# 3_Connectors.net
KiCad netlist of a schematic drawn in Altium Designer
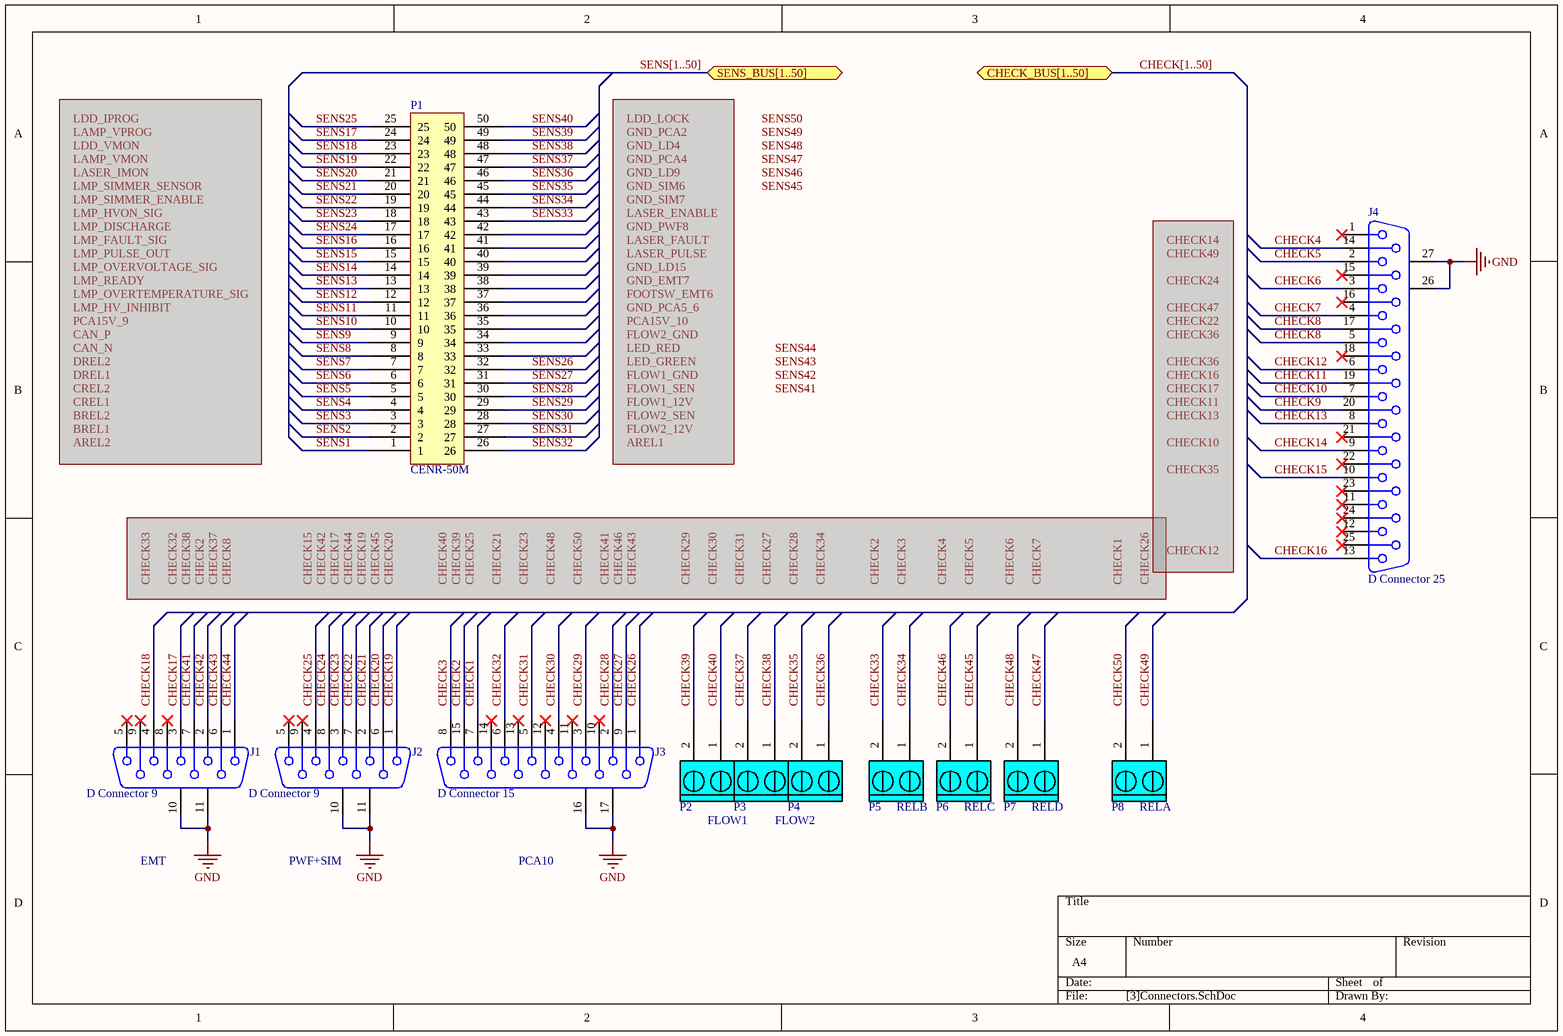
[diagram p0: [3]Connectors.SchDoc]

(export (version "E")
  (design (tool "Eeschema 10.0.6"))
  (components
    (comp (ref "J1")
      (value "D Connector 9")
      (footprint "DSUB1.385-2H9F")
      (description "Receptacle Assembly, 9 Position, Right Angle")
      (fields (field (name "PUBLISHER") "Altium Limited"))
      (libsource (lib "Connectors") (part "D Connector 9"))
    )
    (comp (ref "J2")
      (value "D Connector 9")
      (footprint "DSUB1.385-2H9M")
      (description "Receptacle Assembly, 9 Position, Right Angle")
      (fields (field (name "PUBLISHER") "Altium Limited"))
      (libsource (lib "Connectors") (part "D Connector 9"))
    )
    (comp (ref "J3")
      (value "D Connector 15")
      (footprint "DSUB1.385-2H15M")
      (description "Receptacle Assembly, 15 Position, Right Angle")
      (fields (field (name "PUBLISHER") "Altium Limited"))
      (libsource (lib "Connectors") (part "D Connector 15"))
    )
    (comp (ref "J4")
      (value "D Connector 25")
      (footprint "DSUB1.385-2H25A-F")
      (description "Receptacle Assembly, 25 Position, Right Angle")
      (fields (field (name "PUBLISHER") "Altium Limited"))
      (libsource (lib "Connectors") (part "D Connector 25"))
    )
    (comp (ref "P1")
      (value "CENR-50M")
      (footprint "CENR-50M")
      (libsource (lib "Connectors") (part "CENR-50M"))
    )
    (comp (ref "P2")
      (value "DG340-3.81")
      (footprint "DG340-3.81-02P-00A(H)")
      (description "Terminal block")
      (libsource (lib "Connectors") (part "DG340-3.81-02P"))
    )
    (comp (ref "P3")
      (value "DG340-3.81")
      (footprint "DG340-3.81-02P-00A(H)")
      (description "Terminal block")
      (libsource (lib "Connectors") (part "DG340-3.81-02P"))
    )
    (comp (ref "P4")
      (value "DG340-3.81")
      (footprint "DG340-3.81-02P-00A(H)")
      (description "Terminal block")
      (libsource (lib "Connectors") (part "DG340-3.81-02P"))
    )
    (comp (ref "P5")
      (value "DG340-3.81")
      (footprint "DG340-3.81-02P-00A(H)")
      (description "Terminal block")
      (libsource (lib "Connectors") (part "DG340-3.81-02P"))
    )
    (comp (ref "P6")
      (value "DG340-3.81")
      (footprint "DG340-3.81-02P-00A(H)")
      (description "Terminal block")
      (libsource (lib "Connectors") (part "DG340-3.81-02P"))
    )
    (comp (ref "P7")
      (value "DG340-3.81")
      (footprint "DG340-3.81-02P-00A(H)")
      (description "Terminal block")
      (libsource (lib "Connectors") (part "DG340-3.81-02P"))
    )
    (comp (ref "P8")
      (value "DG340-3.81")
      (footprint "DG340-3.81-02P-00A(H)")
      (description "Terminal block")
      (libsource (lib "Connectors") (part "DG340-3.81-02P"))
    )
  )
  (nets
    (net (code "7") (name "/CHECK1") (class "Default")
      (node (ref "J3") (pin "7") (pinfunction "7_7") (pintype "passive"))
    )
    (net (code "8") (name "/CHECK2") (class "Default")
      (node (ref "J3") (pin "15") (pinfunction "15_15") (pintype "passive"))
    )
    (net (code "9") (name "/CHECK3") (class "Default")
      (node (ref "J3") (pin "8") (pinfunction "8_8") (pintype "passive"))
    )
    (net (code "10") (name "/CHECK4") (class "Default")
      (node (ref "J4") (pin "14") (pinfunction "14_14") (pintype "passive"))
    )
    (net (code "11") (name "/CHECK5") (class "Default")
      (node (ref "J4") (pin "2") (pinfunction "2_2") (pintype "passive"))
    )
    (net (code "12") (name "/CHECK6") (class "Default")
      (node (ref "J4") (pin "3") (pinfunction "3_3") (pintype "passive"))
    )
    (net (code "13") (name "/CHECK7") (class "Default")
      (node (ref "J4") (pin "4") (pinfunction "4_4") (pintype "passive"))
    )
    (net (code "14") (name "/CHECK8") (class "Default")
      (node (ref "J4") (pin "17") (pinfunction "17_17") (pintype "passive"))
      (node (ref "J4") (pin "5") (pinfunction "5_5") (pintype "passive"))
    )
    (net (code "15") (name "/CHECK9") (class "Default")
      (node (ref "J4") (pin "20") (pinfunction "20_20") (pintype "passive"))
    )
    (net (code "16") (name "/CHECK10") (class "Default")
      (node (ref "J4") (pin "7") (pinfunction "7_7") (pintype "passive"))
    )
    (net (code "17") (name "/CHECK11") (class "Default")
      (node (ref "J4") (pin "19") (pinfunction "19_19") (pintype "passive"))
    )
    (net (code "18") (name "/CHECK12") (class "Default")
      (node (ref "J4") (pin "6") (pinfunction "6_6") (pintype "passive"))
    )
    (net (code "19") (name "/CHECK13") (class "Default")
      (node (ref "J4") (pin "8") (pinfunction "8_8") (pintype "passive"))
    )
    (net (code "20") (name "/CHECK14") (class "Default")
      (node (ref "J4") (pin "9") (pinfunction "9_9") (pintype "passive"))
    )
    (net (code "21") (name "/CHECK15") (class "Default")
      (node (ref "J4") (pin "10") (pinfunction "10_10") (pintype "passive"))
    )
    (net (code "22") (name "/CHECK16") (class "Default")
      (node (ref "J4") (pin "13") (pinfunction "13_13") (pintype "passive"))
    )
    (net (code "23") (name "/CHECK17") (class "Default")
      (node (ref "J1") (pin "3") (pinfunction "3_3") (pintype "passive"))
    )
    (net (code "24") (name "/CHECK18") (class "Default")
      (node (ref "J1") (pin "4") (pinfunction "4_4") (pintype "passive"))
    )
    (net (code "25") (name "/CHECK19") (class "Default")
      (node (ref "J2") (pin "1") (pinfunction "1_1") (pintype "passive"))
    )
    (net (code "26") (name "/CHECK20") (class "Default")
      (node (ref "J2") (pin "6") (pinfunction "6_6") (pintype "passive"))
    )
    (net (code "27") (name "/CHECK21") (class "Default")
      (node (ref "J2") (pin "2") (pinfunction "2_2") (pintype "passive"))
    )
    (net (code "28") (name "/CHECK22") (class "Default")
      (node (ref "J2") (pin "7") (pinfunction "7_7") (pintype "passive"))
    )
    (net (code "29") (name "/CHECK23") (class "Default")
      (node (ref "J2") (pin "3") (pinfunction "3_3") (pintype "passive"))
    )
    (net (code "30") (name "/CHECK24") (class "Default")
      (node (ref "J2") (pin "8") (pinfunction "8_8") (pintype "passive"))
    )
    (net (code "31") (name "/CHECK25") (class "Default")
      (node (ref "J2") (pin "4") (pinfunction "4_4") (pintype "passive"))
    )
    (net (code "32") (name "/CHECK26") (class "Default")
      (node (ref "J3") (pin "1") (pinfunction "1_1") (pintype "passive"))
    )
    (net (code "33") (name "/CHECK27") (class "Default")
      (node (ref "J3") (pin "9") (pinfunction "9_9") (pintype "passive"))
    )
    (net (code "34") (name "/CHECK28") (class "Default")
      (node (ref "J3") (pin "2") (pinfunction "2_2") (pintype "passive"))
    )
    (net (code "35") (name "/CHECK29") (class "Default")
      (node (ref "J3") (pin "3") (pinfunction "3_3") (pintype "passive"))
    )
    (net (code "36") (name "/CHECK30") (class "Default")
      (node (ref "J3") (pin "4") (pinfunction "4_4") (pintype "passive"))
    )
    (net (code "37") (name "/CHECK31") (class "Default")
      (node (ref "J3") (pin "5") (pinfunction "5_5") (pintype "passive"))
    )
    (net (code "38") (name "/CHECK32") (class "Default")
      (node (ref "J3") (pin "6") (pinfunction "6_6") (pintype "passive"))
    )
    (net (code "39") (name "/CHECK33") (class "Default")
      (node (ref "P5") (pin "2") (pinfunction "2_2") (pintype "passive"))
    )
    (net (code "40") (name "/CHECK34") (class "Default")
      (node (ref "P5") (pin "1") (pinfunction "1_1") (pintype "passive"))
    )
    (net (code "41") (name "/CHECK35") (class "Default")
      (node (ref "P4") (pin "2") (pinfunction "2_2") (pintype "passive"))
    )
    (net (code "42") (name "/CHECK36") (class "Default")
      (node (ref "P4") (pin "1") (pinfunction "1_1") (pintype "passive"))
    )
    (net (code "43") (name "/CHECK37") (class "Default")
      (node (ref "P3") (pin "2") (pinfunction "2_2") (pintype "passive"))
    )
    (net (code "44") (name "/CHECK38") (class "Default")
      (node (ref "P3") (pin "1") (pinfunction "1_1") (pintype "passive"))
    )
    (net (code "45") (name "/CHECK39") (class "Default")
      (node (ref "P2") (pin "2") (pinfunction "2_2") (pintype "passive"))
    )
    (net (code "46") (name "/CHECK40") (class "Default")
      (node (ref "P2") (pin "1") (pinfunction "1_1") (pintype "passive"))
    )
    (net (code "47") (name "/CHECK41") (class "Default")
      (node (ref "J1") (pin "7") (pinfunction "7_7") (pintype "passive"))
    )
    (net (code "48") (name "/CHECK42") (class "Default")
      (node (ref "J1") (pin "2") (pinfunction "2_2") (pintype "passive"))
    )
    (net (code "49") (name "/CHECK43") (class "Default")
      (node (ref "J1") (pin "6") (pinfunction "6_6") (pintype "passive"))
    )
    (net (code "50") (name "/CHECK44") (class "Default")
      (node (ref "J1") (pin "1") (pinfunction "1_1") (pintype "passive"))
    )
    (net (code "51") (name "/CHECK45") (class "Default")
      (node (ref "P6") (pin "1") (pinfunction "1_1") (pintype "passive"))
    )
    (net (code "52") (name "/CHECK46") (class "Default")
      (node (ref "P6") (pin "2") (pinfunction "2_2") (pintype "passive"))
    )
    (net (code "53") (name "/CHECK47") (class "Default")
      (node (ref "P7") (pin "1") (pinfunction "1_1") (pintype "passive"))
    )
    (net (code "54") (name "/CHECK48") (class "Default")
      (node (ref "P7") (pin "2") (pinfunction "2_2") (pintype "passive"))
    )
    (net (code "55") (name "/CHECK49") (class "Default")
      (node (ref "P8") (pin "1") (pinfunction "1_1") (pintype "passive"))
    )
    (net (code "56") (name "/CHECK50") (class "Default")
      (node (ref "P8") (pin "2") (pinfunction "2_2") (pintype "passive"))
    )
    (net (code "102") (name "/SENS1") (class "Default")
      (node (ref "P1") (pin "1") (pinfunction "1_1") (pintype "passive"))
    )
    (net (code "103") (name "/SENS2") (class "Default")
      (node (ref "P1") (pin "2") (pinfunction "2_2") (pintype "passive"))
    )
    (net (code "104") (name "/SENS3") (class "Default")
      (node (ref "P1") (pin "3") (pinfunction "3_3") (pintype "passive"))
    )
    (net (code "105") (name "/SENS4") (class "Default")
      (node (ref "P1") (pin "4") (pinfunction "4_4") (pintype "passive"))
    )
    (net (code "106") (name "/SENS5") (class "Default")
      (node (ref "P1") (pin "5") (pinfunction "5_5") (pintype "passive"))
    )
    (net (code "107") (name "/SENS6") (class "Default")
      (node (ref "P1") (pin "6") (pinfunction "6_6") (pintype "passive"))
    )
    (net (code "108") (name "/SENS7") (class "Default")
      (node (ref "P1") (pin "7") (pinfunction "7_7") (pintype "passive"))
    )
    (net (code "109") (name "/SENS8") (class "Default")
      (node (ref "P1") (pin "8") (pinfunction "8_8") (pintype "passive"))
    )
    (net (code "110") (name "/SENS9") (class "Default")
      (node (ref "P1") (pin "9") (pinfunction "9_9") (pintype "passive"))
    )
    (net (code "111") (name "/SENS10") (class "Default")
      (node (ref "P1") (pin "10") (pinfunction "10_10") (pintype "passive"))
    )
    (net (code "112") (name "/SENS11") (class "Default")
      (node (ref "P1") (pin "11") (pinfunction "11_11") (pintype "passive"))
    )
    (net (code "113") (name "/SENS12") (class "Default")
      (node (ref "P1") (pin "12") (pinfunction "12_12") (pintype "passive"))
    )
    (net (code "114") (name "/SENS13") (class "Default")
      (node (ref "P1") (pin "13") (pinfunction "13_13") (pintype "passive"))
    )
    (net (code "115") (name "/SENS14") (class "Default")
      (node (ref "P1") (pin "14") (pinfunction "14_14") (pintype "passive"))
    )
    (net (code "116") (name "/SENS15") (class "Default")
      (node (ref "P1") (pin "15") (pinfunction "15_15") (pintype "passive"))
    )
    (net (code "117") (name "/SENS16") (class "Default")
      (node (ref "P1") (pin "16") (pinfunction "16_16") (pintype "passive"))
    )
    (net (code "118") (name "/SENS17") (class "Default")
      (node (ref "P1") (pin "24") (pinfunction "24_24") (pintype "passive"))
    )
    (net (code "119") (name "/SENS18") (class "Default")
      (node (ref "P1") (pin "23") (pinfunction "23_23") (pintype "passive"))
    )
    (net (code "120") (name "/SENS19") (class "Default")
      (node (ref "P1") (pin "22") (pinfunction "22_22") (pintype "passive"))
    )
    (net (code "121") (name "/SENS20") (class "Default")
      (node (ref "P1") (pin "21") (pinfunction "21_21") (pintype "passive"))
    )
    (net (code "122") (name "/SENS21") (class "Default")
      (node (ref "P1") (pin "20") (pinfunction "20_20") (pintype "passive"))
    )
    (net (code "123") (name "/SENS22") (class "Default")
      (node (ref "P1") (pin "19") (pinfunction "19_19") (pintype "passive"))
    )
    (net (code "124") (name "/SENS23") (class "Default")
      (node (ref "P1") (pin "18") (pinfunction "18_18") (pintype "passive"))
    )
    (net (code "125") (name "/SENS24") (class "Default")
      (node (ref "P1") (pin "17") (pinfunction "17_17") (pintype "passive"))
    )
    (net (code "126") (name "/SENS25") (class "Default")
      (node (ref "P1") (pin "25") (pinfunction "25_25") (pintype "passive"))
    )
    (net (code "127") (name "/SENS26") (class "Default")
      (node (ref "P1") (pin "32") (pinfunction "32_32") (pintype "passive"))
    )
    (net (code "128") (name "/SENS27") (class "Default")
      (node (ref "P1") (pin "31") (pinfunction "31_31") (pintype "passive"))
    )
    (net (code "129") (name "/SENS28") (class "Default")
      (node (ref "P1") (pin "30") (pinfunction "30_30") (pintype "passive"))
    )
    (net (code "130") (name "/SENS29") (class "Default")
      (node (ref "P1") (pin "29") (pinfunction "29_29") (pintype "passive"))
    )
    (net (code "131") (name "/SENS30") (class "Default")
      (node (ref "P1") (pin "28") (pinfunction "28_28") (pintype "passive"))
    )
    (net (code "132") (name "/SENS31") (class "Default")
      (node (ref "P1") (pin "27") (pinfunction "27_27") (pintype "passive"))
    )
    (net (code "133") (name "/SENS32") (class "Default")
      (node (ref "P1") (pin "26") (pinfunction "26_26") (pintype "passive"))
    )
    (net (code "134") (name "/SENS33") (class "Default")
      (node (ref "P1") (pin "43") (pinfunction "43_43") (pintype "passive"))
    )
    (net (code "135") (name "/SENS34") (class "Default")
      (node (ref "P1") (pin "44") (pinfunction "44_44") (pintype "passive"))
    )
    (net (code "136") (name "/SENS35") (class "Default")
      (node (ref "P1") (pin "45") (pinfunction "45_45") (pintype "passive"))
    )
    (net (code "137") (name "/SENS36") (class "Default")
      (node (ref "P1") (pin "46") (pinfunction "46_46") (pintype "passive"))
    )
    (net (code "138") (name "/SENS37") (class "Default")
      (node (ref "P1") (pin "47") (pinfunction "47_47") (pintype "passive"))
    )
    (net (code "139") (name "/SENS38") (class "Default")
      (node (ref "P1") (pin "48") (pinfunction "48_48") (pintype "passive"))
    )
    (net (code "140") (name "/SENS39") (class "Default")
      (node (ref "P1") (pin "49") (pinfunction "49_49") (pintype "passive"))
    )
    (net (code "141") (name "/SENS40") (class "Default")
      (node (ref "P1") (pin "50") (pinfunction "50_50") (pintype "passive"))
    )
    (net (code "153") (name "GND") (class "Default")
      (node (ref "J1") (pin "10") (pinfunction "MH1_10") (pintype "passive"))
      (node (ref "J1") (pin "11") (pinfunction "MH2_11") (pintype "passive"))
      (node (ref "J2") (pin "10") (pinfunction "MH1_10") (pintype "passive"))
      (node (ref "J2") (pin "11") (pinfunction "MH2_11") (pintype "passive"))
      (node (ref "J3") (pin "16") (pinfunction "MH1_16") (pintype "passive"))
      (node (ref "J3") (pin "17") (pinfunction "MH2_17") (pintype "passive"))
      (node (ref "J4") (pin "26") (pinfunction "MH1_26") (pintype "passive"))
      (node (ref "J4") (pin "27") (pinfunction "MH2_27") (pintype "passive"))
    )
    (net (code "154") (name "unconnected-(J1-Pad5)") (class "Default")
      (node (ref "J1") (pin "5") (pinfunction "5_5") (pintype "passive+no_connect"))
    )
    (net (code "155") (name "unconnected-(J1-Pad8)") (class "Default")
      (node (ref "J1") (pin "8") (pinfunction "8_8") (pintype "passive+no_connect"))
    )
    (net (code "156") (name "unconnected-(J1-Pad9)") (class "Default")
      (node (ref "J1") (pin "9") (pinfunction "9_9") (pintype "passive+no_connect"))
    )
    (net (code "157") (name "unconnected-(J2-Pad5)") (class "Default")
      (node (ref "J2") (pin "5") (pinfunction "5_5") (pintype "passive+no_connect"))
    )
    (net (code "158") (name "unconnected-(J2-Pad9)") (class "Default")
      (node (ref "J2") (pin "9") (pinfunction "9_9") (pintype "passive+no_connect"))
    )
    (net (code "159") (name "unconnected-(J3-Pad10)") (class "Default")
      (node (ref "J3") (pin "10") (pinfunction "10_10") (pintype "passive+no_connect"))
    )
    (net (code "160") (name "unconnected-(J3-Pad11)") (class "Default")
      (node (ref "J3") (pin "11") (pinfunction "11_11") (pintype "passive+no_connect"))
    )
    (net (code "161") (name "unconnected-(J3-Pad12)") (class "Default")
      (node (ref "J3") (pin "12") (pinfunction "12_12") (pintype "passive+no_connect"))
    )
    (net (code "162") (name "unconnected-(J3-Pad13)") (class "Default")
      (node (ref "J3") (pin "13") (pinfunction "13_13") (pintype "passive+no_connect"))
    )
    (net (code "163") (name "unconnected-(J3-Pad14)") (class "Default")
      (node (ref "J3") (pin "14") (pinfunction "14_14") (pintype "passive+no_connect"))
    )
    (net (code "164") (name "unconnected-(J4-Pad1)") (class "Default")
      (node (ref "J4") (pin "1") (pinfunction "1_1") (pintype "passive+no_connect"))
    )
    (net (code "165") (name "unconnected-(J4-Pad11)") (class "Default")
      (node (ref "J4") (pin "11") (pinfunction "11_11") (pintype "passive+no_connect"))
    )
    (net (code "166") (name "unconnected-(J4-Pad12)") (class "Default")
      (node (ref "J4") (pin "12") (pinfunction "12_12") (pintype "passive+no_connect"))
    )
    (net (code "167") (name "unconnected-(J4-Pad15)") (class "Default")
      (node (ref "J4") (pin "15") (pinfunction "15_15") (pintype "passive+no_connect"))
    )
    (net (code "168") (name "unconnected-(J4-Pad16)") (class "Default")
      (node (ref "J4") (pin "16") (pinfunction "16_16") (pintype "passive+no_connect"))
    )
    (net (code "169") (name "unconnected-(J4-Pad18)") (class "Default")
      (node (ref "J4") (pin "18") (pinfunction "18_18") (pintype "passive+no_connect"))
    )
    (net (code "170") (name "unconnected-(J4-Pad21)") (class "Default")
      (node (ref "J4") (pin "21") (pinfunction "21_21") (pintype "passive+no_connect"))
    )
    (net (code "171") (name "unconnected-(J4-Pad22)") (class "Default")
      (node (ref "J4") (pin "22") (pinfunction "22_22") (pintype "passive+no_connect"))
    )
    (net (code "172") (name "unconnected-(J4-Pad23)") (class "Default")
      (node (ref "J4") (pin "23") (pinfunction "23_23") (pintype "passive+no_connect"))
    )
    (net (code "173") (name "unconnected-(J4-Pad24)") (class "Default")
      (node (ref "J4") (pin "24") (pinfunction "24_24") (pintype "passive+no_connect"))
    )
    (net (code "174") (name "unconnected-(J4-Pad25)") (class "Default")
      (node (ref "J4") (pin "25") (pinfunction "25_25") (pintype "passive+no_connect"))
    )
    (net (code "175") (name "unconnected-(P1-Pad33)") (class "Default")
      (node (ref "P1") (pin "33") (pinfunction "33_33") (pintype "passive"))
    )
    (net (code "176") (name "unconnected-(P1-Pad34)") (class "Default")
      (node (ref "P1") (pin "34") (pinfunction "34_34") (pintype "passive"))
    )
    (net (code "177") (name "unconnected-(P1-Pad35)") (class "Default")
      (node (ref "P1") (pin "35") (pinfunction "35_35") (pintype "passive"))
    )
    (net (code "178") (name "unconnected-(P1-Pad36)") (class "Default")
      (node (ref "P1") (pin "36") (pinfunction "36_36") (pintype "passive"))
    )
    (net (code "179") (name "unconnected-(P1-Pad37)") (class "Default")
      (node (ref "P1") (pin "37") (pinfunction "37_37") (pintype "passive"))
    )
    (net (code "180") (name "unconnected-(P1-Pad38)") (class "Default")
      (node (ref "P1") (pin "38") (pinfunction "38_38") (pintype "passive"))
    )
    (net (code "181") (name "unconnected-(P1-Pad39)") (class "Default")
      (node (ref "P1") (pin "39") (pinfunction "39_39") (pintype "passive"))
    )
    (net (code "182") (name "unconnected-(P1-Pad40)") (class "Default")
      (node (ref "P1") (pin "40") (pinfunction "40_40") (pintype "passive"))
    )
    (net (code "183") (name "unconnected-(P1-Pad41)") (class "Default")
      (node (ref "P1") (pin "41") (pinfunction "41_41") (pintype "passive"))
    )
    (net (code "184") (name "unconnected-(P1-Pad42)") (class "Default")
      (node (ref "P1") (pin "42") (pinfunction "42_42") (pintype "passive"))
    )
  )
)
